# SHIEL_V0_01.net
KiCad netlist of a schematic drawn in EAGLE
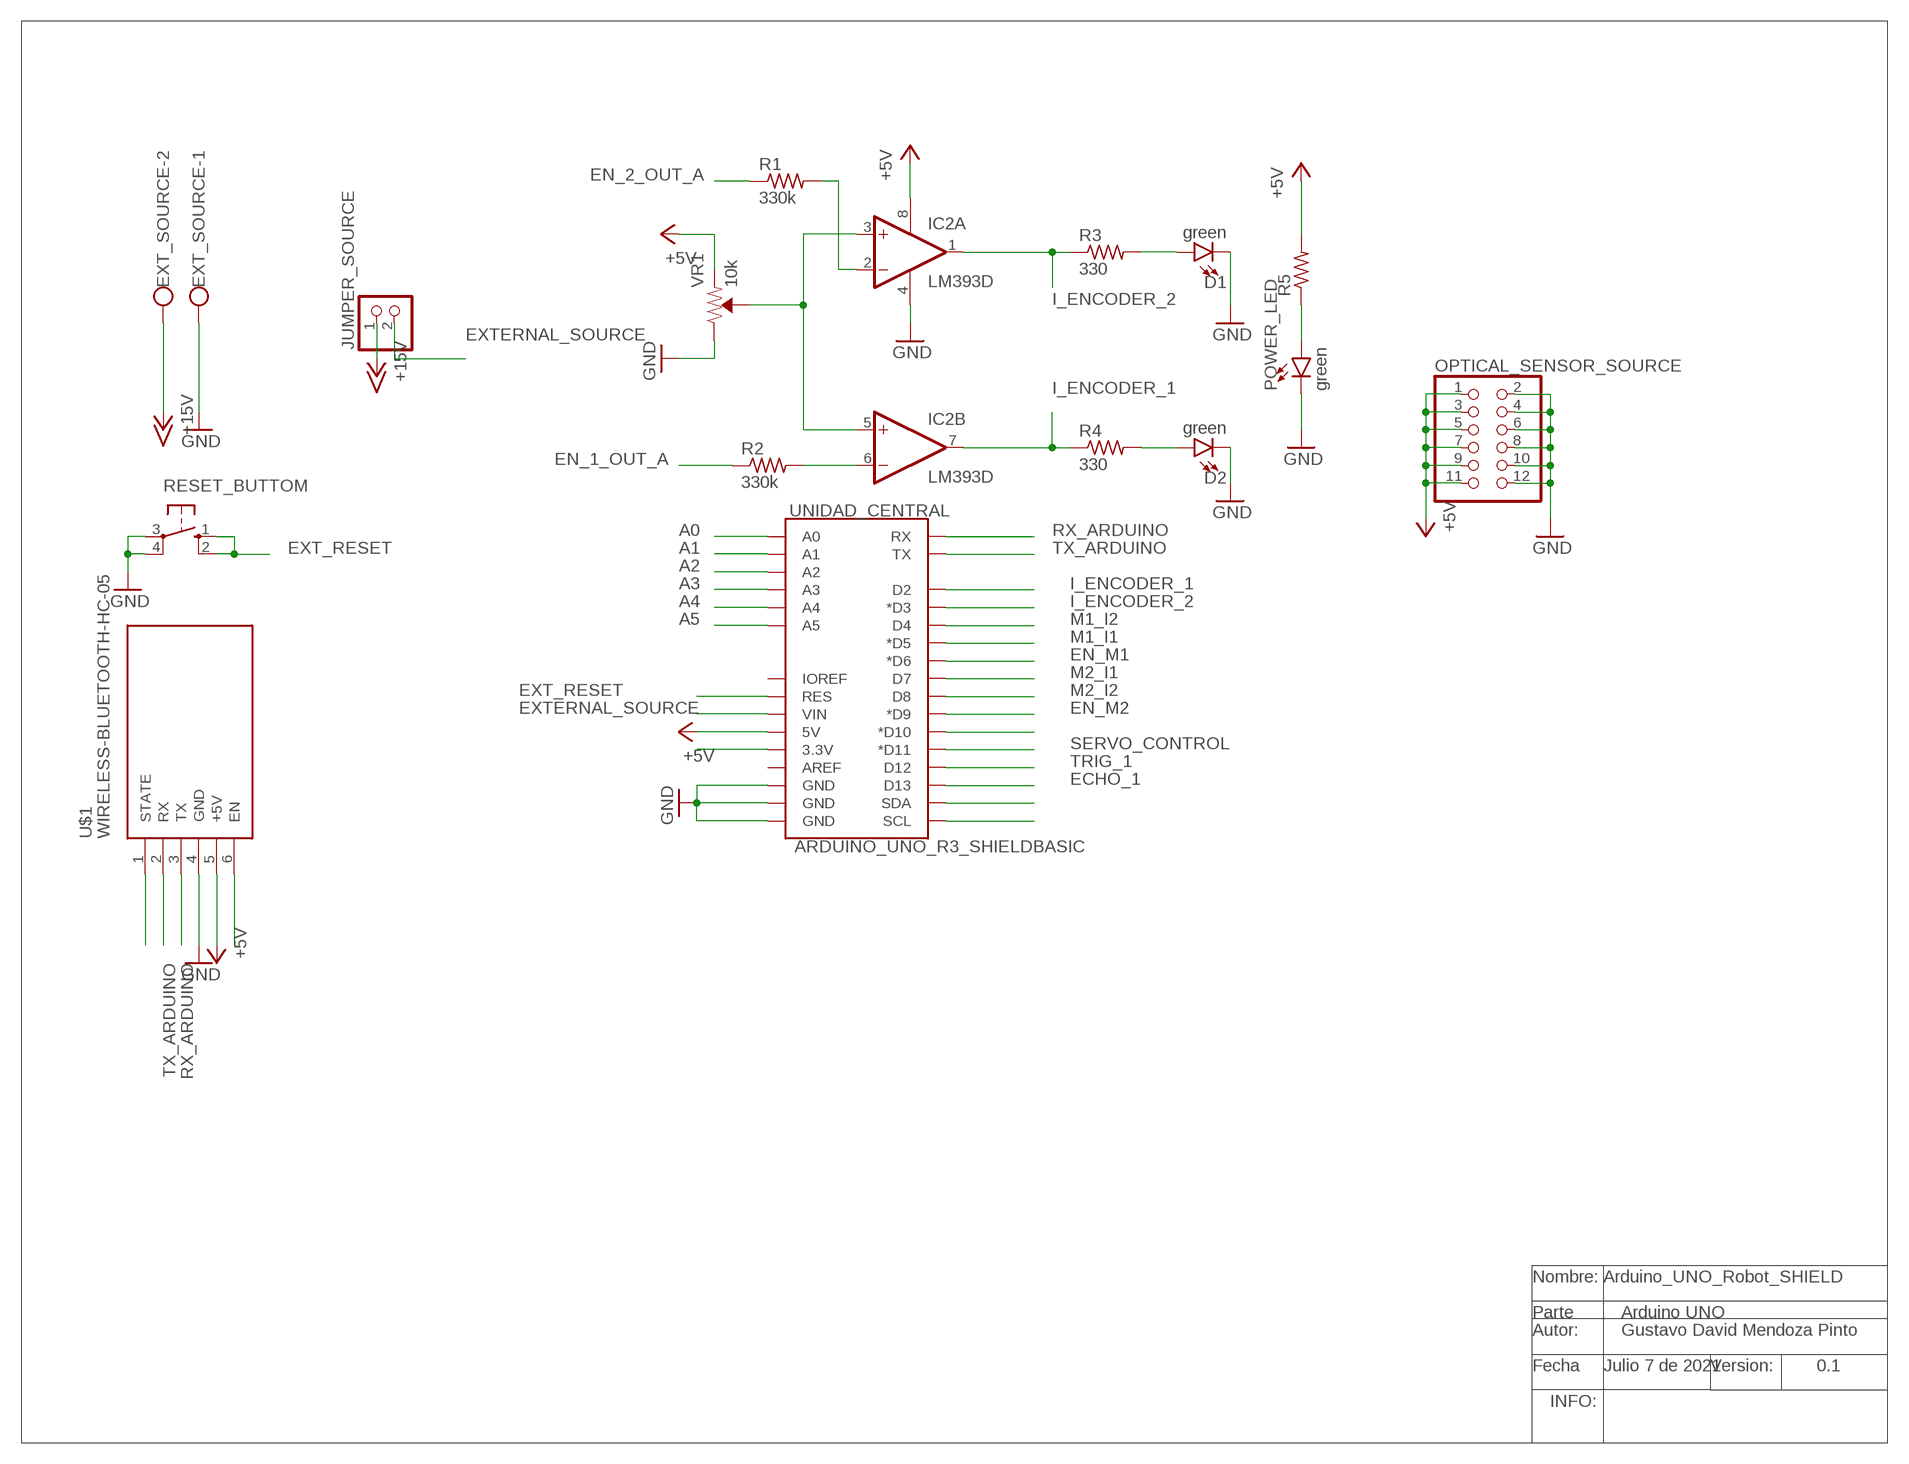
[diagram p0: schematic, sheet 1]
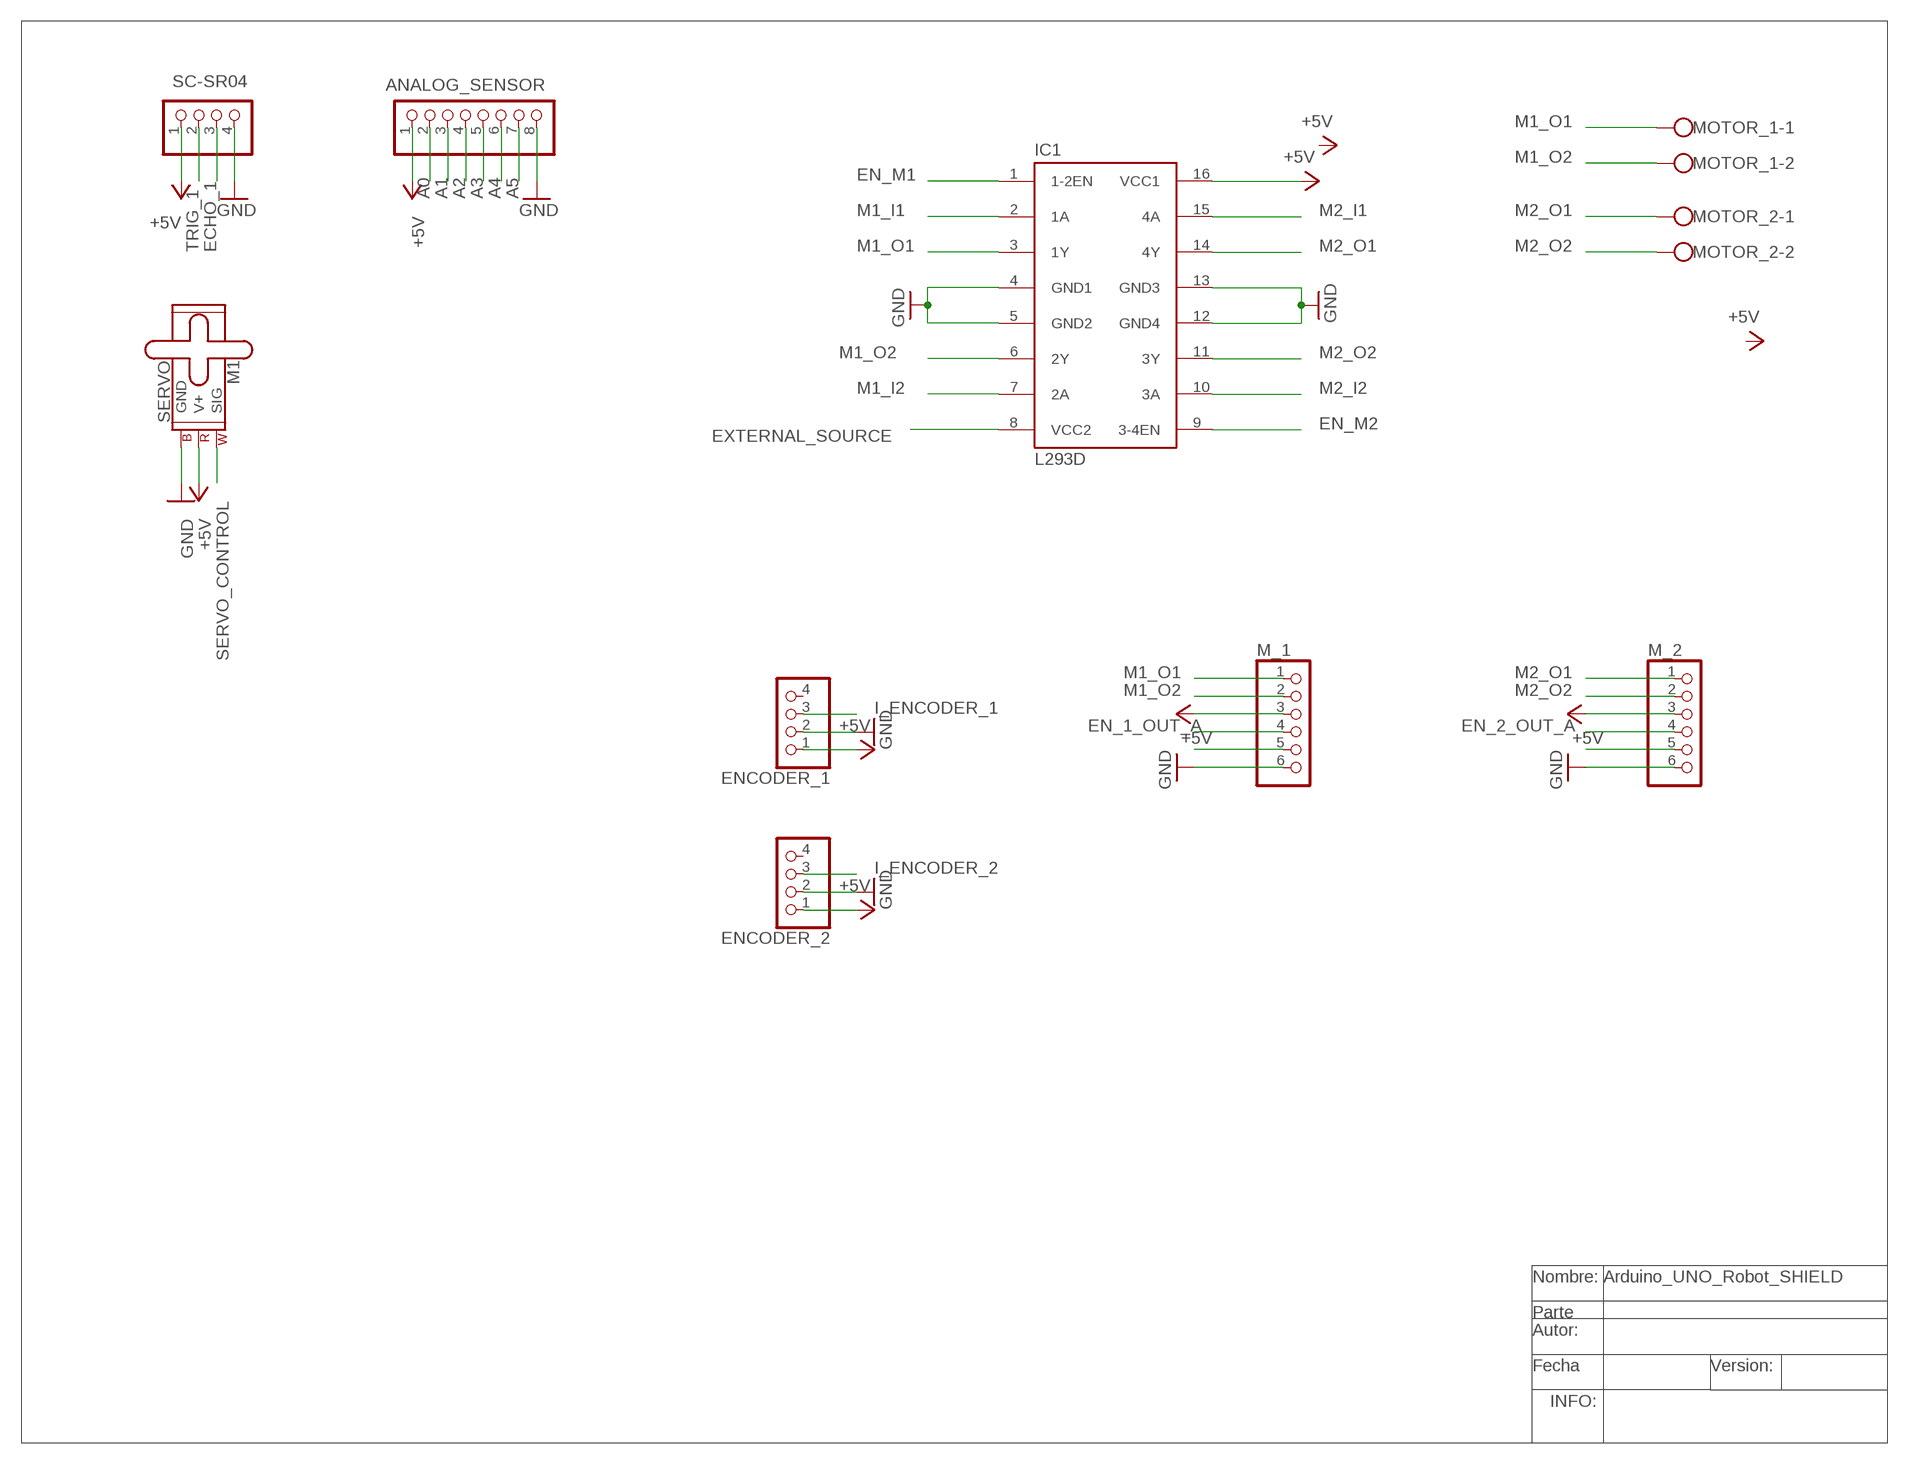
[diagram p1: schematic, sheet 2]

(export (version "E")
  (design (tool "Eeschema 10.0.6"))
  (components
    (comp (ref "D1")
      (value "green")
      (footprint "eagle-import:LED_3MM-NS")
      (libsource (lib "eagle-import") (part "LED-3MM-NO_SILK"))
    )
    (comp (ref "D2")
      (value "green")
      (footprint "eagle-import:LED_3MM-NS")
      (libsource (lib "eagle-import") (part "LED-3MM-NO_SILK"))
    )
    (comp (ref "EXT_SOURCE")
      (value "W237-102")
      (footprint "eagle-import:W237-102")
      (fields (field (name "MPN") "237-102"))
      (libsource (lib "eagle-import") (part "W237-102"))
    )
    (comp (ref "IC2")
      (value "LM393D")
      (footprint "eagle-import:SO08")
      (libsource (lib "eagle-import") (part "LM393D"))
    )
    (comp (ref "JUMPER_SOURCE")
      (value "PINHD-1X2")
      (footprint "eagle-import:1X02")
      (libsource (lib "eagle-import") (part "PINHD-1X2"))
    )
    (comp (ref "OPTICAL_SENSOR_SOURCE")
      (value "PINHD-2X6")
      (footprint "eagle-import:2X06")
      (libsource (lib "eagle-import") (part "PINHD-2X6"))
    )
    (comp (ref "POWER_LED")
      (value "green")
      (footprint "eagle-import:LED_3MM-NS")
      (libsource (lib "eagle-import") (part "LED-3MM-NO_SILK"))
    )
    (comp (ref "R1")
      (value "330k")
      (footprint "eagle-import:M2012")
      (libsource (lib "eagle-import") (part "R-US_M2012"))
    )
    (comp (ref "R2")
      (value "330k")
      (footprint "eagle-import:M2012")
      (libsource (lib "eagle-import") (part "R-US_M2012"))
    )
    (comp (ref "R3")
      (value "330")
      (footprint "eagle-import:M2012")
      (libsource (lib "eagle-import") (part "R-US_M2012"))
    )
    (comp (ref "R4")
      (value "330")
      (footprint "eagle-import:M2012")
      (libsource (lib "eagle-import") (part "R-US_M2012"))
    )
    (comp (ref "R5")
      (value "R-US_M2012")
      (footprint "eagle-import:M2012")
      (libsource (lib "eagle-import") (part "R-US_M2012"))
    )
    (comp (ref "RESET_BUTTOM")
      (value "10-XX")
      (footprint "eagle-import:B3F-10XX")
      (fields (field (name "MPN") "B3F-1000"))
      (libsource (lib "eagle-import") (part "10-XX"))
    )
    (comp (ref "U$1")
      (value "WIRELESS-BLUETOOTH-HC-05")
      (footprint "eagle-import:WIRELESS-BLUETOOTH-HC-05")
      (libsource (lib "eagle-import") (part "WIRELESS-BLUETOOTH-HC-05"))
    )
    (comp (ref "UNIDAD_CENTRAL")
      (value "ARDUINO_UNO_R3_SHIELDBASIC")
      (footprint "eagle-import:UNO_R3_SHIELD")
      (libsource (lib "eagle-import") (part "ARDUINO_UNO_R3_SHIELDBASIC"))
    )
    (comp (ref "VR1")
      (value "10k")
      (footprint "eagle-import:TRIMPOT-PTH-3386U")
      (libsource (lib "eagle-import") (part "TRIMPOT-PTH-10MM-KNOB-1/2W-10%"))
    )
    (comp (ref "ANALOG_SENSOR")
      (value "PINHD-1X8")
      (footprint "eagle-import:1X08")
      (libsource (lib "eagle-import") (part "PINHD-1X8"))
    )
    (comp (ref "ENCODER_1")
      (value "PINHD-1X4")
      (footprint "eagle-import:1X04")
      (libsource (lib "eagle-import") (part "PINHD-1X4"))
    )
    (comp (ref "ENCODER_2")
      (value "PINHD-1X4")
      (footprint "eagle-import:1X04")
      (libsource (lib "eagle-import") (part "PINHD-1X4"))
    )
    (comp (ref "IC1")
      (value "L293D")
      (footprint "eagle-import:DIL16")
      (libsource (lib "eagle-import") (part "L293D"))
    )
    (comp (ref "M1")
      (value "SERVO")
      (footprint "eagle-import:1X03")
      (libsource (lib "eagle-import") (part "SERVO"))
    )
    (comp (ref "MOTOR_1")
      (value "W237-102")
      (footprint "eagle-import:W237-102")
      (fields (field (name "MPN") "237-102"))
      (libsource (lib "eagle-import") (part "W237-102"))
    )
    (comp (ref "MOTOR_2")
      (value "W237-102")
      (footprint "eagle-import:W237-102")
      (fields (field (name "MPN") "237-102"))
      (libsource (lib "eagle-import") (part "W237-102"))
    )
    (comp (ref "M_1")
      (value "PINHD-1X6")
      (footprint "eagle-import:1X06")
      (libsource (lib "eagle-import") (part "PINHD-1X6"))
    )
    (comp (ref "M_2")
      (value "PINHD-1X6")
      (footprint "eagle-import:1X06")
      (libsource (lib "eagle-import") (part "PINHD-1X6"))
    )
    (comp (ref "SC-SR04")
      (value "PINHD-1X4")
      (footprint "eagle-import:1X04")
      (libsource (lib "eagle-import") (part "PINHD-1X4"))
    )
  )
  (nets
    (net (code "1") (name "+5V") (class "Default")
      (node (ref "ANALOG_SENSOR") (pin "1") (pinfunction "1_1") (pintype "passive"))
      (node (ref "ENCODER_1") (pin "1") (pinfunction "1_1") (pintype "passive"))
      (node (ref "ENCODER_2") (pin "1") (pinfunction "1_1") (pintype "passive"))
      (node (ref "IC1") (pin "16") (pinfunction "VCC1_16") (pintype "power_in"))
      (node (ref "IC2") (pin "8") (pinfunction "V+_8") (pintype "power_in"))
      (node (ref "M1") (pin "2") (pinfunction "V+_2") (pintype "bidirectional"))
      (node (ref "M_1") (pin "3") (pinfunction "3_3") (pintype "passive"))
      (node (ref "M_2") (pin "3") (pinfunction "3_3") (pintype "passive"))
      (node (ref "OPTICAL_SENSOR_SOURCE") (pin "1") (pinfunction "1_1") (pintype "passive"))
      (node (ref "OPTICAL_SENSOR_SOURCE") (pin "11") (pinfunction "11_11") (pintype "passive"))
      (node (ref "OPTICAL_SENSOR_SOURCE") (pin "3") (pinfunction "3_3") (pintype "passive"))
      (node (ref "OPTICAL_SENSOR_SOURCE") (pin "5") (pinfunction "5_5") (pintype "passive"))
      (node (ref "OPTICAL_SENSOR_SOURCE") (pin "7") (pinfunction "7_7") (pintype "passive"))
      (node (ref "OPTICAL_SENSOR_SOURCE") (pin "9") (pinfunction "9_9") (pintype "passive"))
      (node (ref "R5") (pin "2") (pinfunction "2_2") (pintype "passive"))
      (node (ref "SC-SR04") (pin "1") (pinfunction "1_1") (pintype "passive"))
      (node (ref "U$1") (pin "5") (pinfunction "+5V_5") (pintype "power_in"))
      (node (ref "UNIDAD_CENTRAL") (pin "5V") (pinfunction "5V_5V") (pintype "bidirectional"))
      (node (ref "VR1") (pin "1") (pinfunction "CCW_1") (pintype "passive"))
    )
    (net (code "2") (name "+15V") (class "Default")
      (node (ref "EXT_SOURCE") (pin "2") (pinfunction "KL_2") (pintype "passive"))
      (node (ref "JUMPER_SOURCE") (pin "1") (pinfunction "1_1") (pintype "passive"))
    )
    (net (code "3") (name "A0") (class "Default")
      (node (ref "ANALOG_SENSOR") (pin "2") (pinfunction "2_2") (pintype "passive"))
      (node (ref "UNIDAD_CENTRAL") (pin "A0") (pinfunction "A0_A0") (pintype "bidirectional"))
    )
    (net (code "4") (name "A1") (class "Default")
      (node (ref "ANALOG_SENSOR") (pin "3") (pinfunction "3_3") (pintype "passive"))
      (node (ref "UNIDAD_CENTRAL") (pin "A1") (pinfunction "A1_A1") (pintype "bidirectional"))
    )
    (net (code "5") (name "A2") (class "Default")
      (node (ref "ANALOG_SENSOR") (pin "4") (pinfunction "4_4") (pintype "passive"))
      (node (ref "UNIDAD_CENTRAL") (pin "A2") (pinfunction "A2_A2") (pintype "bidirectional"))
    )
    (net (code "6") (name "A3") (class "Default")
      (node (ref "ANALOG_SENSOR") (pin "5") (pinfunction "5_5") (pintype "passive"))
      (node (ref "UNIDAD_CENTRAL") (pin "A3") (pinfunction "A3_A3") (pintype "bidirectional"))
    )
    (net (code "7") (name "A4") (class "Default")
      (node (ref "ANALOG_SENSOR") (pin "6") (pinfunction "6_6") (pintype "passive"))
      (node (ref "UNIDAD_CENTRAL") (pin "A4") (pinfunction "A4_A4") (pintype "bidirectional"))
    )
    (net (code "8") (name "A5") (class "Default")
      (node (ref "ANALOG_SENSOR") (pin "7") (pinfunction "7_7") (pintype "passive"))
      (node (ref "UNIDAD_CENTRAL") (pin "A5") (pinfunction "A5_A5") (pintype "bidirectional"))
    )
    (net (code "9") (name "ECHO_1") (class "Default")
      (node (ref "SC-SR04") (pin "3") (pinfunction "3_3") (pintype "passive"))
      (node (ref "UNIDAD_CENTRAL") (pin "D13") (pinfunction "D13_D13") (pintype "bidirectional"))
    )
    (net (code "10") (name "EN_1_OUT_A") (class "Default")
      (node (ref "M_1") (pin "4") (pinfunction "4_4") (pintype "passive"))
      (node (ref "R2") (pin "1") (pinfunction "1_1") (pintype "passive"))
    )
    (net (code "11") (name "EN_2_OUT_A") (class "Default")
      (node (ref "M_2") (pin "4") (pinfunction "4_4") (pintype "passive"))
      (node (ref "R1") (pin "1") (pinfunction "1_1") (pintype "passive"))
    )
    (net (code "12") (name "EN_M1") (class "Default")
      (node (ref "IC1") (pin "1") (pinfunction "1-2EN_1") (pintype "input"))
      (node (ref "UNIDAD_CENTRAL") (pin "D6") (pinfunction "*D6_D6") (pintype "bidirectional"))
    )
    (net (code "13") (name "EN_M2") (class "Default")
      (node (ref "IC1") (pin "9") (pinfunction "3-4EN_9") (pintype "input"))
      (node (ref "UNIDAD_CENTRAL") (pin "D9") (pinfunction "*D9_D9") (pintype "bidirectional"))
    )
    (net (code "14") (name "EXTERNAL_SOURCE") (class "Default")
      (node (ref "IC1") (pin "8") (pinfunction "VCC2_8") (pintype "power_in"))
      (node (ref "JUMPER_SOURCE") (pin "2") (pinfunction "2_2") (pintype "passive"))
      (node (ref "UNIDAD_CENTRAL") (pin "VIN") (pinfunction "VIN_VIN") (pintype "bidirectional"))
    )
    (net (code "15") (name "EXT_RESET") (class "Default")
      (node (ref "RESET_BUTTOM") (pin "1") (pinfunction "S_1") (pintype "passive"))
      (node (ref "RESET_BUTTOM") (pin "2") (pinfunction "S1_2") (pintype "passive"))
      (node (ref "UNIDAD_CENTRAL") (pin "RES") (pinfunction "RES_RES") (pintype "bidirectional"))
    )
    (net (code "16") (name "GND") (class "Default")
      (node (ref "ANALOG_SENSOR") (pin "8") (pinfunction "8_8") (pintype "passive"))
      (node (ref "D1") (pin "K") (pinfunction "C_K") (pintype "passive"))
      (node (ref "D2") (pin "K") (pinfunction "C_K") (pintype "passive"))
      (node (ref "ENCODER_1") (pin "2") (pinfunction "2_2") (pintype "passive"))
      (node (ref "ENCODER_2") (pin "2") (pinfunction "2_2") (pintype "passive"))
      (node (ref "EXT_SOURCE") (pin "1") (pinfunction "KL_1") (pintype "passive"))
      (node (ref "IC1") (pin "12") (pinfunction "GND4_12") (pintype "power_in"))
      (node (ref "IC1") (pin "13") (pinfunction "GND3_13") (pintype "power_in"))
      (node (ref "IC1") (pin "4") (pinfunction "GND1_4") (pintype "power_in"))
      (node (ref "IC1") (pin "5") (pinfunction "GND2_5") (pintype "power_in"))
      (node (ref "IC2") (pin "4") (pinfunction "V-_4") (pintype "power_in"))
      (node (ref "M1") (pin "3") (pinfunction "GND_3") (pintype "bidirectional"))
      (node (ref "M_1") (pin "6") (pinfunction "6_6") (pintype "passive"))
      (node (ref "M_2") (pin "6") (pinfunction "6_6") (pintype "passive"))
      (node (ref "OPTICAL_SENSOR_SOURCE") (pin "10") (pinfunction "10_10") (pintype "passive"))
      (node (ref "OPTICAL_SENSOR_SOURCE") (pin "12") (pinfunction "12_12") (pintype "passive"))
      (node (ref "OPTICAL_SENSOR_SOURCE") (pin "2") (pinfunction "2_2") (pintype "passive"))
      (node (ref "OPTICAL_SENSOR_SOURCE") (pin "4") (pinfunction "4_4") (pintype "passive"))
      (node (ref "OPTICAL_SENSOR_SOURCE") (pin "6") (pinfunction "6_6") (pintype "passive"))
      (node (ref "OPTICAL_SENSOR_SOURCE") (pin "8") (pinfunction "8_8") (pintype "passive"))
      (node (ref "POWER_LED") (pin "K") (pinfunction "C_K") (pintype "passive"))
      (node (ref "RESET_BUTTOM") (pin "3") (pinfunction "P_3") (pintype "passive"))
      (node (ref "RESET_BUTTOM") (pin "4") (pinfunction "P1_4") (pintype "passive"))
      (node (ref "SC-SR04") (pin "4") (pinfunction "4_4") (pintype "passive"))
      (node (ref "U$1") (pin "4") (pinfunction "GND_4") (pintype "power_in"))
      (node (ref "UNIDAD_CENTRAL") (pin "GND@0") (pinfunction "GND_GND@0") (pintype "bidirectional"))
      (node (ref "UNIDAD_CENTRAL") (pin "GND@1") (pinfunction "GND_GND@1") (pintype "bidirectional"))
      (node (ref "UNIDAD_CENTRAL") (pin "GND@2") (pinfunction "GND_GND@2") (pintype "bidirectional"))
      (node (ref "VR1") (pin "3") (pinfunction "CW_3") (pintype "passive"))
    )
    (net (code "17") (name "I_ENCODER_1") (class "Default")
      (node (ref "ENCODER_1") (pin "3") (pinfunction "3_3") (pintype "passive"))
      (node (ref "IC2") (pin "7") (pinfunction "OUT_7") (pintype "output"))
      (node (ref "R4") (pin "1") (pinfunction "1_1") (pintype "passive"))
      (node (ref "UNIDAD_CENTRAL") (pin "D2") (pinfunction "D2_D2") (pintype "bidirectional"))
    )
    (net (code "18") (name "I_ENCODER_2") (class "Default")
      (node (ref "ENCODER_2") (pin "3") (pinfunction "3_3") (pintype "passive"))
      (node (ref "IC2") (pin "1") (pinfunction "OUT_1") (pintype "output"))
      (node (ref "R3") (pin "1") (pinfunction "1_1") (pintype "passive"))
      (node (ref "UNIDAD_CENTRAL") (pin "D3") (pinfunction "*D3_D3") (pintype "bidirectional"))
    )
    (net (code "19") (name "M1_I1") (class "Default")
      (node (ref "IC1") (pin "2") (pinfunction "1A_2") (pintype "input"))
      (node (ref "UNIDAD_CENTRAL") (pin "D5") (pinfunction "*D5_D5") (pintype "bidirectional"))
    )
    (net (code "20") (name "M1_I2") (class "Default")
      (node (ref "IC1") (pin "7") (pinfunction "2A_7") (pintype "input"))
      (node (ref "UNIDAD_CENTRAL") (pin "D4") (pinfunction "D4_D4") (pintype "bidirectional"))
    )
    (net (code "21") (name "M1_O1") (class "Default")
      (node (ref "IC1") (pin "3") (pinfunction "1Y_3") (pintype "output"))
      (node (ref "MOTOR_1") (pin "1") (pinfunction "KL_1") (pintype "passive"))
      (node (ref "M_1") (pin "1") (pinfunction "1_1") (pintype "passive"))
    )
    (net (code "22") (name "M1_O2") (class "Default")
      (node (ref "IC1") (pin "6") (pinfunction "2Y_6") (pintype "output"))
      (node (ref "MOTOR_1") (pin "2") (pinfunction "KL_2") (pintype "passive"))
      (node (ref "M_1") (pin "2") (pinfunction "2_2") (pintype "passive"))
    )
    (net (code "23") (name "M2_I1") (class "Default")
      (node (ref "IC1") (pin "15") (pinfunction "4A_15") (pintype "input"))
      (node (ref "UNIDAD_CENTRAL") (pin "D7") (pinfunction "D7_D7") (pintype "bidirectional"))
    )
    (net (code "24") (name "M2_I2") (class "Default")
      (node (ref "IC1") (pin "10") (pinfunction "3A_10") (pintype "input"))
      (node (ref "UNIDAD_CENTRAL") (pin "D8") (pinfunction "D8_D8") (pintype "bidirectional"))
    )
    (net (code "25") (name "M2_O1") (class "Default")
      (node (ref "IC1") (pin "14") (pinfunction "4Y_14") (pintype "output"))
      (node (ref "MOTOR_2") (pin "1") (pinfunction "KL_1") (pintype "passive"))
      (node (ref "M_2") (pin "1") (pinfunction "1_1") (pintype "passive"))
    )
    (net (code "26") (name "M2_O2") (class "Default")
      (node (ref "IC1") (pin "11") (pinfunction "3Y_11") (pintype "output"))
      (node (ref "MOTOR_2") (pin "2") (pinfunction "KL_2") (pintype "passive"))
      (node (ref "M_2") (pin "2") (pinfunction "2_2") (pintype "passive"))
    )
    (net (code "27") (name "Net-(D1-PadA)") (class "Default")
      (node (ref "D1") (pin "A") (pinfunction "A_A") (pintype "passive"))
      (node (ref "R3") (pin "2") (pinfunction "2_2") (pintype "passive"))
    )
    (net (code "28") (name "Net-(D2-PadA)") (class "Default")
      (node (ref "D2") (pin "A") (pinfunction "A_A") (pintype "passive"))
      (node (ref "R4") (pin "2") (pinfunction "2_2") (pintype "passive"))
    )
    (net (code "29") (name "Net-(IC2A-+IN)") (class "Default")
      (node (ref "IC2") (pin "3") (pinfunction "+IN_3") (pintype "input"))
      (node (ref "IC2") (pin "5") (pinfunction "+IN_5") (pintype "input"))
      (node (ref "VR1") (pin "2") (pinfunction "WIPER_2") (pintype "passive"))
    )
    (net (code "30") (name "Net-(IC2A--IN)") (class "Default")
      (node (ref "IC2") (pin "2") (pinfunction "-IN_2") (pintype "input"))
      (node (ref "R1") (pin "2") (pinfunction "2_2") (pintype "passive"))
    )
    (net (code "31") (name "Net-(IC2B--IN)") (class "Default")
      (node (ref "IC2") (pin "6") (pinfunction "-IN_6") (pintype "input"))
      (node (ref "R2") (pin "2") (pinfunction "2_2") (pintype "passive"))
    )
    (net (code "32") (name "Net-(POWER_LED-PadA)") (class "Default")
      (node (ref "POWER_LED") (pin "A") (pinfunction "A_A") (pintype "passive"))
      (node (ref "R5") (pin "1") (pinfunction "1_1") (pintype "passive"))
    )
    (net (code "33") (name "RX_ARDUINO") (class "Default")
      (node (ref "U$1") (pin "3") (pinfunction "TX_3") (pintype "bidirectional"))
      (node (ref "UNIDAD_CENTRAL") (pin "RX") (pinfunction "RX_RX") (pintype "bidirectional"))
    )
    (net (code "34") (name "SERVO_CONTROL") (class "Default")
      (node (ref "M1") (pin "1") (pinfunction "SIG_1") (pintype "bidirectional"))
      (node (ref "UNIDAD_CENTRAL") (pin "D11") (pinfunction "*D11_D11") (pintype "bidirectional"))
    )
    (net (code "35") (name "TRIG_1") (class "Default")
      (node (ref "SC-SR04") (pin "2") (pinfunction "2_2") (pintype "passive"))
      (node (ref "UNIDAD_CENTRAL") (pin "D12") (pinfunction "D12_D12") (pintype "bidirectional"))
    )
    (net (code "36") (name "TX_ARDUINO") (class "Default")
      (node (ref "U$1") (pin "2") (pinfunction "RX_2") (pintype "bidirectional"))
      (node (ref "UNIDAD_CENTRAL") (pin "TX") (pinfunction "TX_TX") (pintype "bidirectional"))
    )
    (net (code "37") (name "unconnected-(ENCODER_1-Pad4)") (class "Default")
      (node (ref "ENCODER_1") (pin "4") (pinfunction "4_4") (pintype "passive"))
    )
    (net (code "38") (name "unconnected-(ENCODER_2-Pad4)") (class "Default")
      (node (ref "ENCODER_2") (pin "4") (pinfunction "4_4") (pintype "passive"))
    )
    (net (code "39") (name "unconnected-(M_1-Pad5)") (class "Default")
      (node (ref "M_1") (pin "5") (pinfunction "5_5") (pintype "passive"))
    )
    (net (code "40") (name "unconnected-(M_2-Pad5)") (class "Default")
      (node (ref "M_2") (pin "5") (pinfunction "5_5") (pintype "passive"))
    )
    (net (code "41") (name "unconnected-(U$1-EN-Pad6)") (class "Default")
      (node (ref "U$1") (pin "6") (pinfunction "EN_6") (pintype "bidirectional"))
    )
    (net (code "42") (name "unconnected-(U$1-STATE-Pad1)") (class "Default")
      (node (ref "U$1") (pin "1") (pinfunction "STATE_1") (pintype "bidirectional"))
    )
    (net (code "43") (name "unconnected-(UNIDAD_CENTRAL-*D10-PadD10)") (class "Default")
      (node (ref "UNIDAD_CENTRAL") (pin "D10") (pinfunction "*D10_D10") (pintype "bidirectional"))
    )
    (net (code "44") (name "unconnected-(UNIDAD_CENTRAL-Pad3.3V)") (class "Default")
      (node (ref "UNIDAD_CENTRAL") (pin "3.3V") (pinfunction "3.3V_3.3V") (pintype "bidirectional"))
    )
    (net (code "45") (name "unconnected-(UNIDAD_CENTRAL-PadAREF)") (class "Default")
      (node (ref "UNIDAD_CENTRAL") (pin "AREF") (pinfunction "AREF_AREF") (pintype "bidirectional"))
    )
    (net (code "46") (name "unconnected-(UNIDAD_CENTRAL-PadIOREF)") (class "Default")
      (node (ref "UNIDAD_CENTRAL") (pin "IOREF") (pinfunction "IOREF_IOREF") (pintype "bidirectional"))
    )
    (net (code "47") (name "unconnected-(UNIDAD_CENTRAL-PadSCL)") (class "Default")
      (node (ref "UNIDAD_CENTRAL") (pin "SCL") (pinfunction "SCL_SCL") (pintype "bidirectional"))
    )
    (net (code "48") (name "unconnected-(UNIDAD_CENTRAL-PadSDA)") (class "Default")
      (node (ref "UNIDAD_CENTRAL") (pin "SDA") (pinfunction "SDA_SDA") (pintype "bidirectional"))
    )
  )
)
